# SCH_esphome-ajax_2022-05-22.net
KiCad netlist of a schematic drawn in EasyEDA
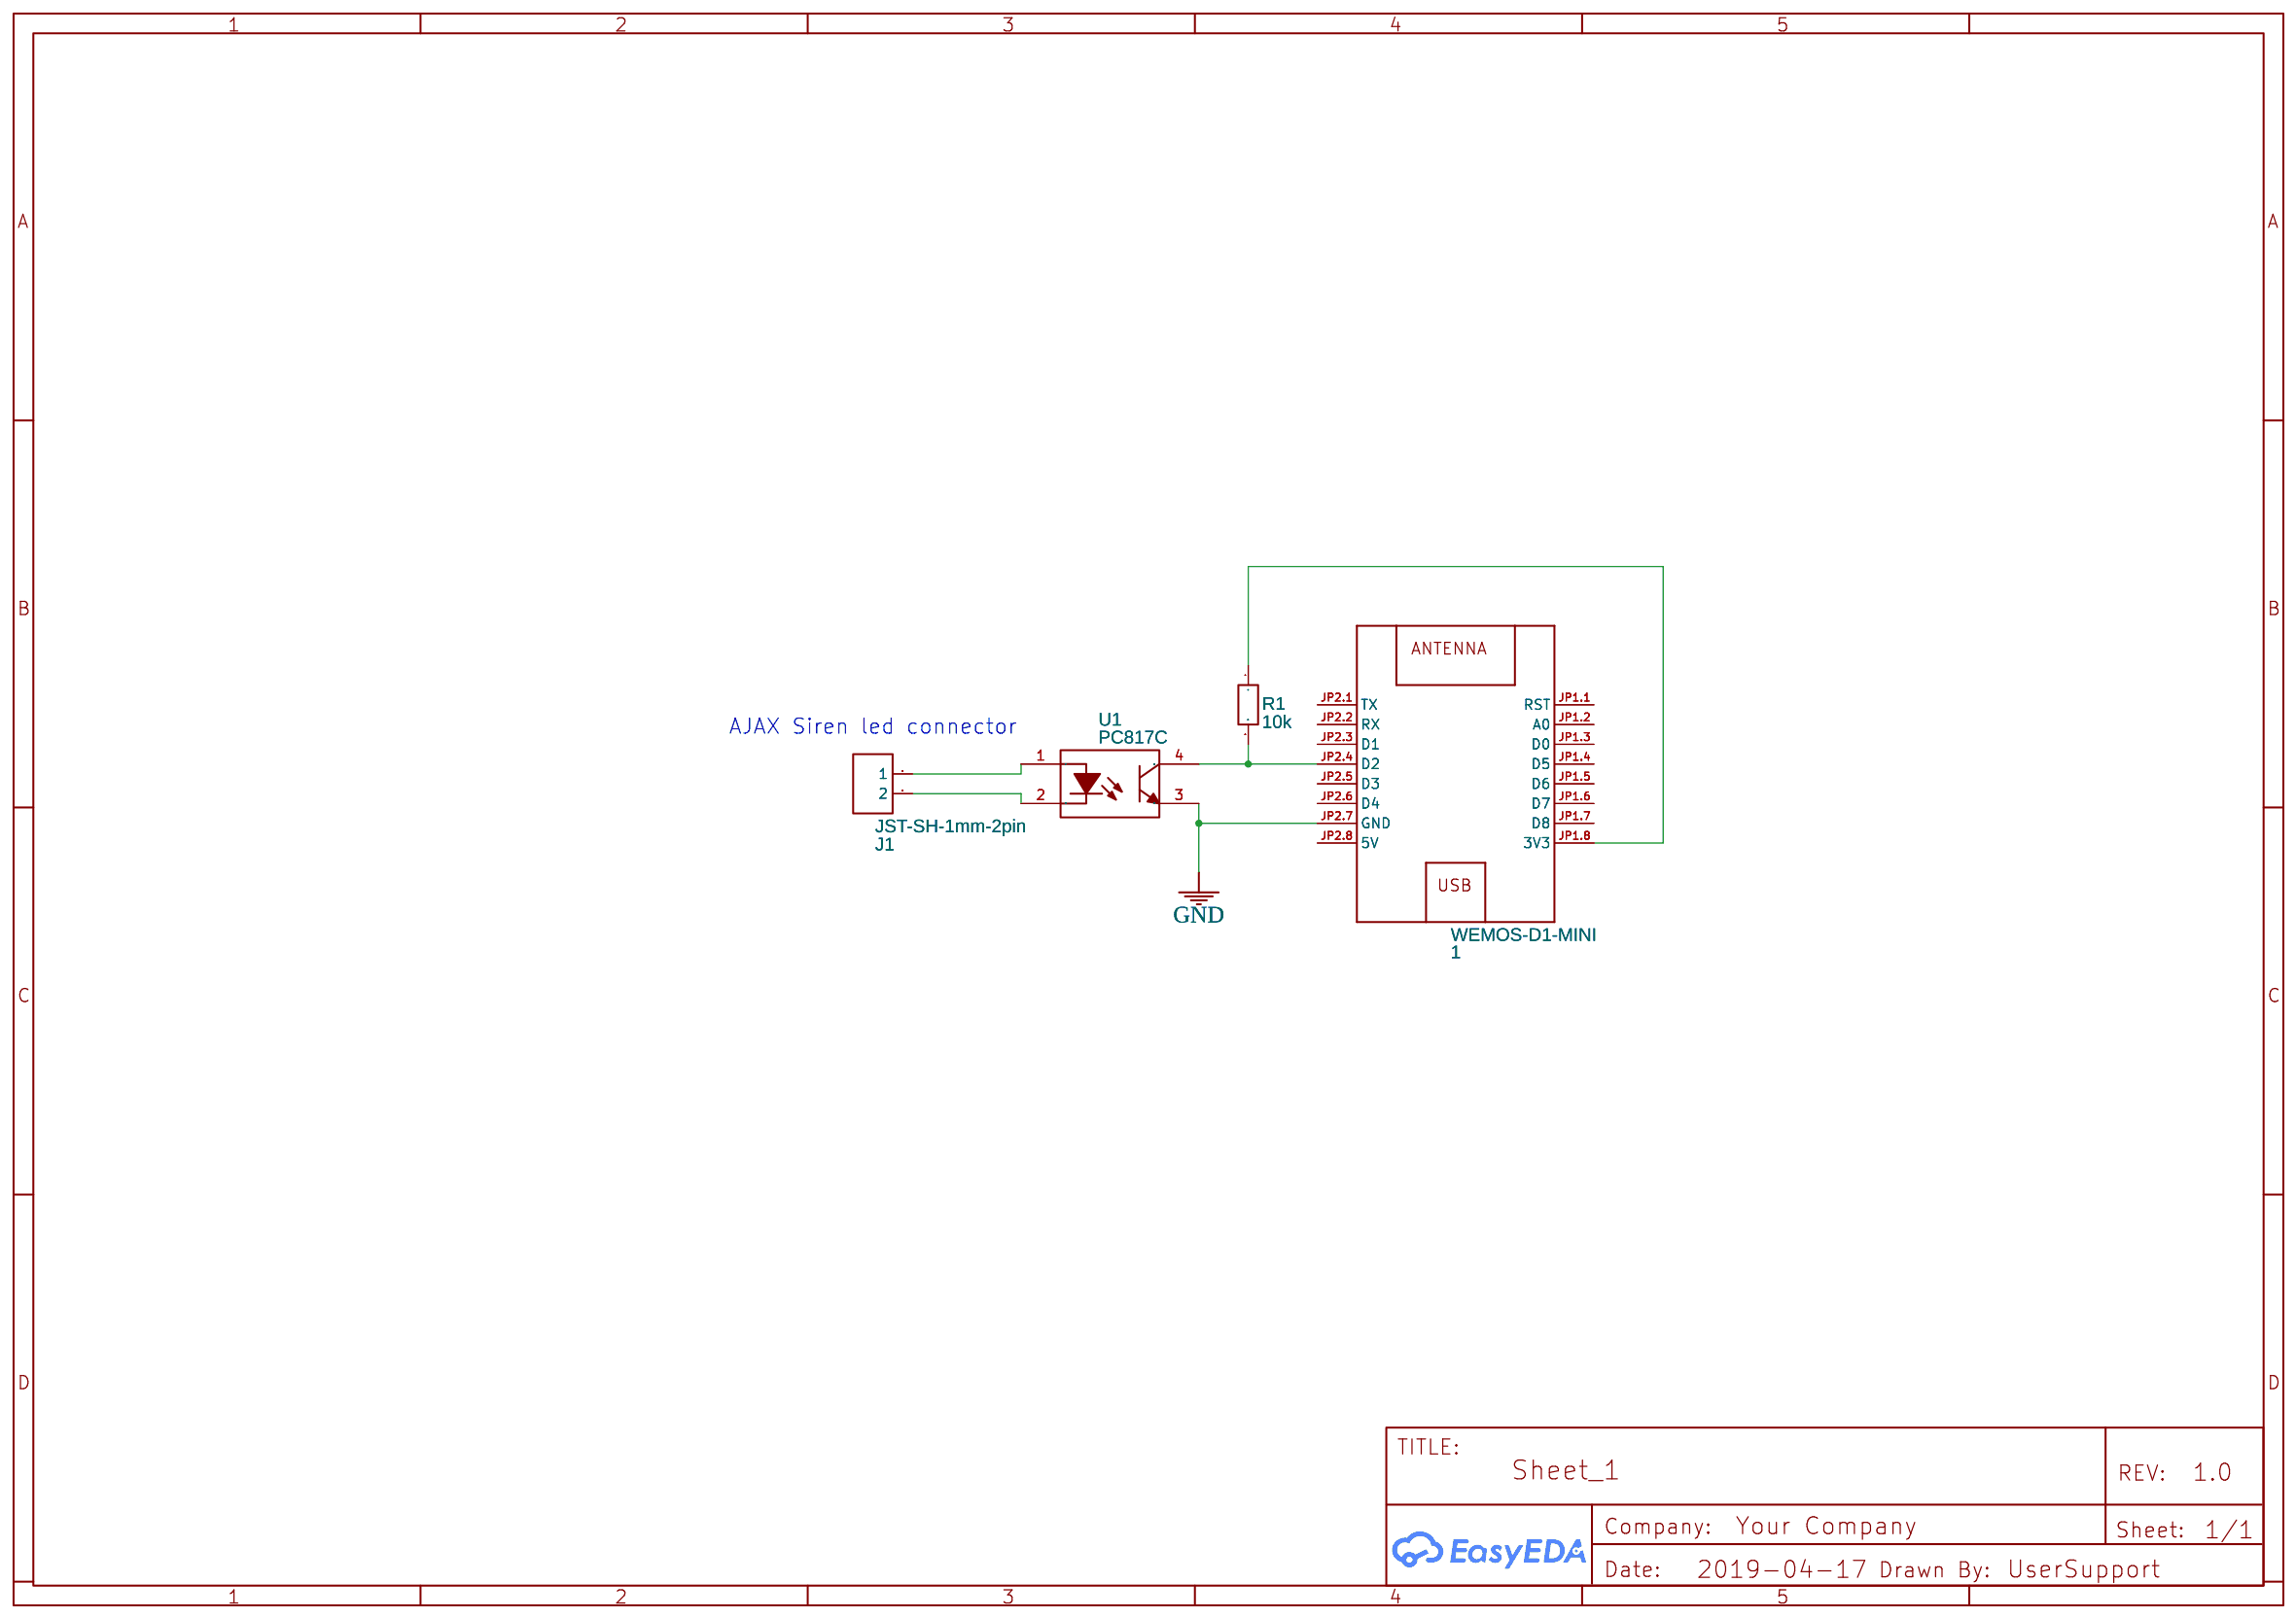
[diagram p0: schematic sheet]

(export (version "E")
  (design (tool "Eeschema 10.0.6"))
  (components
    (comp (ref "1") (value "WEMOS-D1-MINI") (libsource (lib "") (part "WEMOS-D1-MINI")))
    (comp (ref "J1")
      (value "JST-SH-1mm-2pin")
      (fields (field (name "BOM_Supplier Part") "C124375"))
      (libsource (lib "") (part "jst-sh-2p-ver"))
    )
    (comp (ref "R1") (value "10k") (libsource (lib "") (part "R_AXIAL-0.4_EU")))
    (comp (ref "U1")
      (value "PC817C")
      (fields (field (name "BOM_Supplier Part") "C115500"))
      (libsource (lib "") (part "Unknown_550_390"))
    )
  )
  (nets
    (net (code "1") (name "GND") (class "Default")
      (node (ref "1") (pin "JP2.7") (pinfunction "GND_JP2.7") (pintype "bidirectional"))
      (node (ref "U1") (pin "3") (pinfunction "EM_3") (pintype "unspecified"))
    )
    (net (code "2") (name "Net-(1-3V3)") (class "Default")
      (node (ref "1") (pin "JP1.8") (pinfunction "3V3_JP1.8") (pintype "bidirectional"))
      (node (ref "R1") (pin "1") (pinfunction "1_1") (pintype "unspecified"))
    )
    (net (code "3") (name "Net-(1-D2)") (class "Default")
      (node (ref "1") (pin "JP2.4") (pinfunction "D2_JP2.4") (pintype "bidirectional"))
      (node (ref "R1") (pin "2") (pinfunction "2_2") (pintype "unspecified"))
      (node (ref "U1") (pin "4") (pinfunction "COL_4") (pintype "unspecified"))
    )
    (net (code "4") (name "Net-(U1-AN)") (class "Default")
      (node (ref "J1") (pin "1") (pinfunction "1_1") (pintype "unspecified"))
      (node (ref "U1") (pin "1") (pinfunction "AN_1") (pintype "unspecified"))
    )
    (net (code "5") (name "Net-(U1-CAT)") (class "Default")
      (node (ref "J1") (pin "2") (pinfunction "2_2") (pintype "unspecified"))
      (node (ref "U1") (pin "2") (pinfunction "CAT_2") (pintype "unspecified"))
    )
    (net (code "6") (name "unconnected-(1-5V-PadJP2.8)") (class "Default")
      (node (ref "1") (pin "JP2.8") (pinfunction "5V_JP2.8") (pintype "bidirectional"))
    )
    (net (code "7") (name "unconnected-(1-A0-PadJP1.2)") (class "Default")
      (node (ref "1") (pin "JP1.2") (pinfunction "A0_JP1.2") (pintype "bidirectional"))
    )
    (net (code "8") (name "unconnected-(1-D0-PadJP1.3)") (class "Default")
      (node (ref "1") (pin "JP1.3") (pinfunction "D0_JP1.3") (pintype "bidirectional"))
    )
    (net (code "9") (name "unconnected-(1-D1-PadJP2.3)") (class "Default")
      (node (ref "1") (pin "JP2.3") (pinfunction "D1_JP2.3") (pintype "bidirectional"))
    )
    (net (code "10") (name "unconnected-(1-D3-PadJP2.5)") (class "Default")
      (node (ref "1") (pin "JP2.5") (pinfunction "D3_JP2.5") (pintype "bidirectional"))
    )
    (net (code "11") (name "unconnected-(1-D4-PadJP2.6)") (class "Default")
      (node (ref "1") (pin "JP2.6") (pinfunction "D4_JP2.6") (pintype "bidirectional"))
    )
    (net (code "12") (name "unconnected-(1-D5-PadJP1.4)") (class "Default")
      (node (ref "1") (pin "JP1.4") (pinfunction "D5_JP1.4") (pintype "bidirectional"))
    )
    (net (code "13") (name "unconnected-(1-D6-PadJP1.5)") (class "Default")
      (node (ref "1") (pin "JP1.5") (pinfunction "D6_JP1.5") (pintype "bidirectional"))
    )
    (net (code "14") (name "unconnected-(1-D7-PadJP1.6)") (class "Default")
      (node (ref "1") (pin "JP1.6") (pinfunction "D7_JP1.6") (pintype "bidirectional"))
    )
    (net (code "15") (name "unconnected-(1-D8-PadJP1.7)") (class "Default")
      (node (ref "1") (pin "JP1.7") (pinfunction "D8_JP1.7") (pintype "bidirectional"))
    )
    (net (code "16") (name "unconnected-(1-RST-PadJP1.1)") (class "Default")
      (node (ref "1") (pin "JP1.1") (pinfunction "RST_JP1.1") (pintype "bidirectional"))
    )
    (net (code "17") (name "unconnected-(1-RX-PadJP2.2)") (class "Default")
      (node (ref "1") (pin "JP2.2") (pinfunction "RX_JP2.2") (pintype "bidirectional"))
    )
    (net (code "18") (name "unconnected-(1-TX-PadJP2.1)") (class "Default")
      (node (ref "1") (pin "JP2.1") (pinfunction "TX_JP2.1") (pintype "bidirectional"))
    )
  )
)
